# MYC_Homematic_FS20.net
KiCad netlist of a schematic drawn in EAGLE
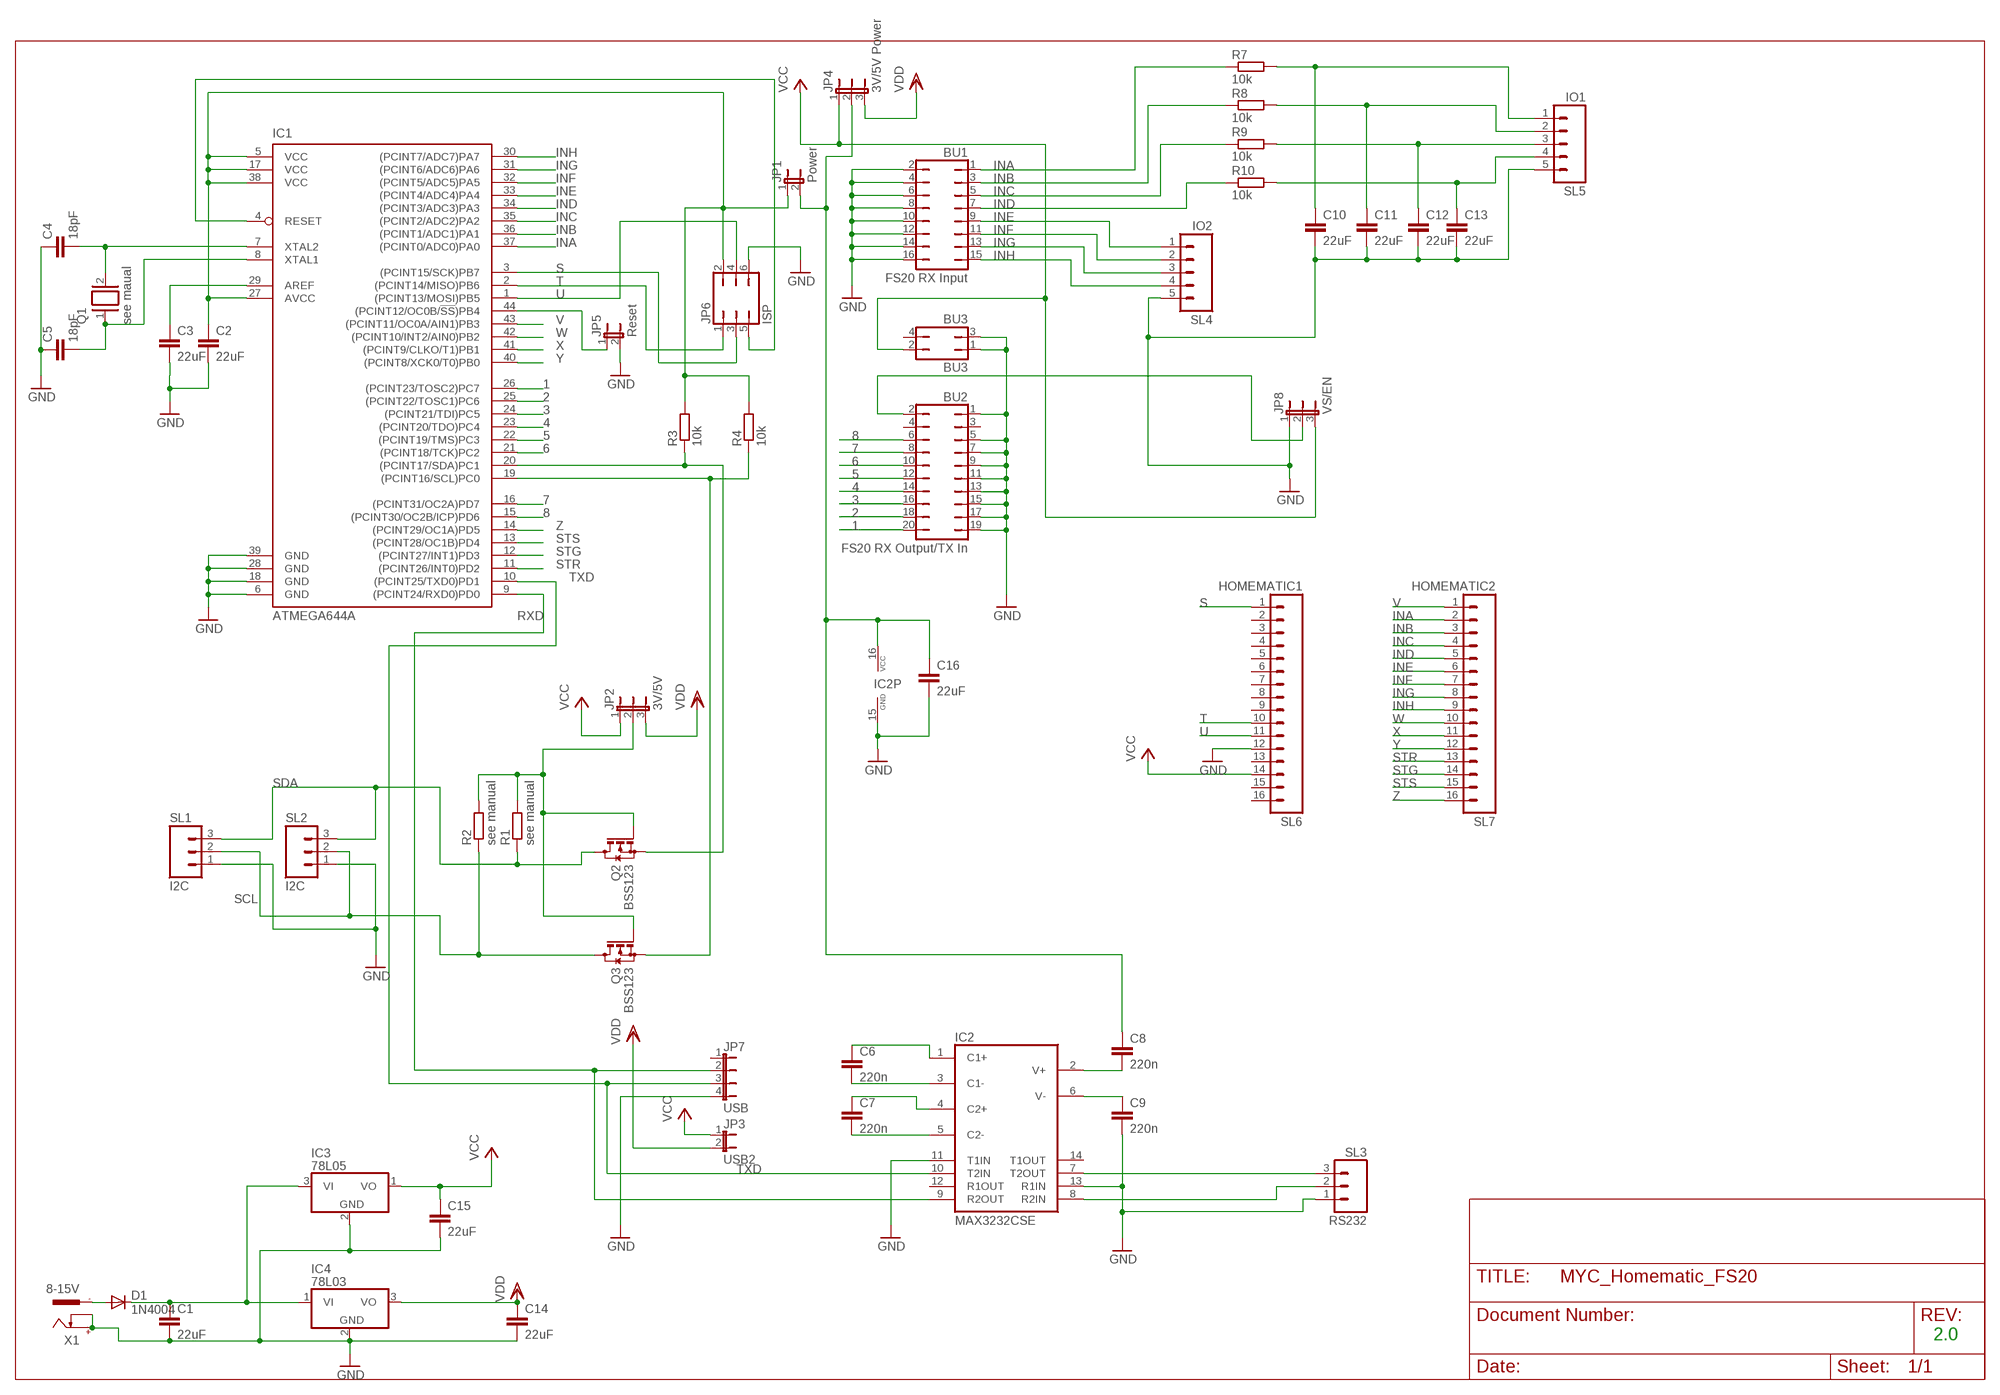
[diagram p0: schematic, sheet 1]

(export (version "E")
  (design (tool "Eeschema 10.0.6"))
  (components
    (comp (ref "BU1")
      (value "FS20 RX Input")
      (footprint "eagle-import:JP8Q")
      (libsource (lib "eagle-import") (part "JP8Q"))
    )
    (comp (ref "BU2")
      (value "FS20 RX Output/TX In")
      (footprint "eagle-import:JP10Q")
      (libsource (lib "eagle-import") (part "JP10Q"))
    )
    (comp (ref "BU3")
      (value "BU3")
      (footprint "eagle-import:JP2Q")
      (libsource (lib "eagle-import") (part "JP2Q"))
    )
    (comp (ref "C1")
      (value "22uF")
      (footprint "eagle-import:C1206")
      (libsource (lib "eagle-import") (part "C-EUC1206"))
    )
    (comp (ref "C2")
      (value "22uF")
      (footprint "eagle-import:C1206")
      (libsource (lib "eagle-import") (part "C-EUC1206"))
    )
    (comp (ref "C3")
      (value "22uF")
      (footprint "eagle-import:C1206")
      (libsource (lib "eagle-import") (part "C-EUC1206"))
    )
    (comp (ref "C4")
      (value "18pF")
      (footprint "eagle-import:C025-030X050")
      (libsource (lib "eagle-import") (part "C-EU025-030X050"))
    )
    (comp (ref "C5")
      (value "18pF")
      (footprint "eagle-import:C025-030X050")
      (libsource (lib "eagle-import") (part "C-EU025-030X050"))
    )
    (comp (ref "C6")
      (value "220n")
      (footprint "eagle-import:C1206")
      (libsource (lib "eagle-import") (part "C-EUC1206"))
    )
    (comp (ref "C7")
      (value "220n")
      (footprint "eagle-import:C1206")
      (libsource (lib "eagle-import") (part "C-EUC1206"))
    )
    (comp (ref "C8")
      (value "220n")
      (footprint "eagle-import:C1206")
      (libsource (lib "eagle-import") (part "C-EUC1206"))
    )
    (comp (ref "C9")
      (value "220n")
      (footprint "eagle-import:C1206")
      (libsource (lib "eagle-import") (part "C-EUC1206"))
    )
    (comp (ref "C10")
      (value "22uF")
      (footprint "eagle-import:C1206")
      (libsource (lib "eagle-import") (part "C-EUC1206"))
    )
    (comp (ref "C11")
      (value "22uF")
      (footprint "eagle-import:C1206")
      (libsource (lib "eagle-import") (part "C-EUC1206"))
    )
    (comp (ref "C12")
      (value "22uF")
      (footprint "eagle-import:C1206")
      (libsource (lib "eagle-import") (part "C-EUC1206"))
    )
    (comp (ref "C13")
      (value "22uF")
      (footprint "eagle-import:C1206")
      (libsource (lib "eagle-import") (part "C-EUC1206"))
    )
    (comp (ref "C14")
      (value "22uF")
      (footprint "eagle-import:C1206")
      (libsource (lib "eagle-import") (part "C-EUC1206"))
    )
    (comp (ref "C15")
      (value "22uF")
      (footprint "eagle-import:C1206")
      (libsource (lib "eagle-import") (part "C-EUC1206"))
    )
    (comp (ref "C16")
      (value "22uF")
      (footprint "eagle-import:C1206")
      (libsource (lib "eagle-import") (part "C-EUC1206"))
    )
    (comp (ref "D1")
      (value "1N4004")
      (footprint "eagle-import:DO41-10")
      (libsource (lib "eagle-import") (part "1N4004"))
    )
    (comp (ref "IC1")
      (value "ATMEGA644A")
      (footprint "eagle-import:TQFP44")
      (fields (field (name "MPN") "ATMEGA644PV-10AU"))
      (libsource (lib "eagle-import") (part "ATMEGA644A"))
    )
    (comp (ref "IC2")
      (value "MAX3232CSE")
      (footprint "eagle-import:SO16")
      (libsource (lib "eagle-import") (part "MAX3232SEC"))
    )
    (comp (ref "IC3")
      (value "78L05")
      (footprint "eagle-import:TO92")
      (libsource (lib "eagle-import") (part "78L05"))
    )
    (comp (ref "IC4")
      (value "78L03")
      (footprint "eagle-import:TO220V")
      (libsource (lib "eagle-import") (part "78TV05"))
    )
    (comp (ref "JP1")
      (value "Power")
      (footprint "eagle-import:JP1")
      (libsource (lib "eagle-import") (part "JP1E"))
    )
    (comp (ref "JP2")
      (value "3V/5V")
      (footprint "eagle-import:JP2")
      (libsource (lib "eagle-import") (part "JP2E"))
    )
    (comp (ref "JP3")
      (value "USB2")
      (footprint "eagle-import:JP1")
      (libsource (lib "eagle-import") (part "JP1E"))
    )
    (comp (ref "JP4")
      (value "3V/5V Power")
      (footprint "eagle-import:JP2")
      (libsource (lib "eagle-import") (part "JP2E"))
    )
    (comp (ref "JP5")
      (value "Reset")
      (footprint "eagle-import:JP1")
      (libsource (lib "eagle-import") (part "JP1E"))
    )
    (comp (ref "JP6")
      (value "ISP")
      (footprint "eagle-import:JP3Q")
      (libsource (lib "eagle-import") (part "JP3Q"))
    )
    (comp (ref "JP7")
      (value "USB")
      (footprint "eagle-import:JP4")
      (libsource (lib "eagle-import") (part "JP4E"))
    )
    (comp (ref "JP8")
      (value "VS/EN")
      (footprint "eagle-import:JP2")
      (libsource (lib "eagle-import") (part "JP2E"))
    )
    (comp (ref "Q1")
      (value "see maual")
      (footprint "eagle-import:QS")
      (libsource (lib "eagle-import") (part "XTAL/S"))
    )
    (comp (ref "Q2")
      (value "BSS123")
      (footprint "eagle-import:SOT23")
      (libsource (lib "eagle-import") (part "BSS123"))
    )
    (comp (ref "Q3")
      (value "BSS123")
      (footprint "eagle-import:SOT23")
      (libsource (lib "eagle-import") (part "BSS123"))
    )
    (comp (ref "R1")
      (value "see manual")
      (footprint "eagle-import:R1206")
      (libsource (lib "eagle-import") (part "R-EU_R1206"))
    )
    (comp (ref "R2")
      (value "see manual")
      (footprint "eagle-import:R1206")
      (libsource (lib "eagle-import") (part "R-EU_R1206"))
    )
    (comp (ref "R3")
      (value "10k")
      (footprint "eagle-import:R1206")
      (libsource (lib "eagle-import") (part "R-EU_R1206"))
    )
    (comp (ref "R4")
      (value "10k")
      (footprint "eagle-import:R1206")
      (libsource (lib "eagle-import") (part "R-EU_R1206"))
    )
    (comp (ref "R7")
      (value "10k")
      (footprint "eagle-import:R1206")
      (libsource (lib "eagle-import") (part "R-EU_R1206"))
    )
    (comp (ref "R8")
      (value "10k")
      (footprint "eagle-import:R1206")
      (libsource (lib "eagle-import") (part "R-EU_R1206"))
    )
    (comp (ref "R9")
      (value "10k")
      (footprint "eagle-import:R1206")
      (libsource (lib "eagle-import") (part "R-EU_R1206"))
    )
    (comp (ref "R10")
      (value "10k")
      (footprint "eagle-import:R1206")
      (libsource (lib "eagle-import") (part "R-EU_R1206"))
    )
    (comp (ref "SL1")
      (value "I2C")
      (footprint "eagle-import:03P")
      (libsource (lib "eagle-import") (part "M03"))
    )
    (comp (ref "SL2")
      (value "I2C")
      (footprint "eagle-import:03P")
      (libsource (lib "eagle-import") (part "M03"))
    )
    (comp (ref "SL3")
      (value "RS232")
      (footprint "eagle-import:03P")
      (libsource (lib "eagle-import") (part "M03"))
    )
    (comp (ref "SL4")
      (value "IO2")
      (footprint "eagle-import:05P")
      (libsource (lib "eagle-import") (part "M05"))
    )
    (comp (ref "SL5")
      (value "IO1")
      (footprint "eagle-import:05P")
      (libsource (lib "eagle-import") (part "M05"))
    )
    (comp (ref "SL6")
      (value "HOMEMATIC1")
      (footprint "eagle-import:16P")
      (libsource (lib "eagle-import") (part "M16"))
    )
    (comp (ref "SL7")
      (value "HOMEMATIC2")
      (footprint "eagle-import:16P")
      (libsource (lib "eagle-import") (part "M16"))
    )
    (comp (ref "X1")
      (value "8-15V")
      (footprint "eagle-import:737992-5")
      (libsource (lib "eagle-import") (part "737992-55"))
    )
  )
  (nets
    (net (code "1") (name "/1") (class "Default")
      (node (ref "BU2") (pin "20") (pinfunction "20_20") (pintype "passive"))
      (node (ref "IC1") (pin "26") (pinfunction "(PCINT23/TOSC2)PC7_26") (pintype "output"))
    )
    (net (code "2") (name "/2") (class "Default")
      (node (ref "BU2") (pin "18") (pinfunction "18_18") (pintype "passive"))
      (node (ref "IC1") (pin "25") (pinfunction "(PCINT22/TOSC1)PC6_25") (pintype "output"))
    )
    (net (code "3") (name "/3") (class "Default")
      (node (ref "BU2") (pin "16") (pinfunction "16_16") (pintype "passive"))
      (node (ref "IC1") (pin "24") (pinfunction "(PCINT21/TDI)PC5_24") (pintype "output"))
    )
    (net (code "4") (name "/4") (class "Default")
      (node (ref "BU2") (pin "14") (pinfunction "14_14") (pintype "passive"))
      (node (ref "IC1") (pin "23") (pinfunction "(PCINT20/TDO)PC4_23") (pintype "output"))
    )
    (net (code "5") (name "/5") (class "Default")
      (node (ref "BU2") (pin "12") (pinfunction "12_12") (pintype "passive"))
      (node (ref "IC1") (pin "22") (pinfunction "(PCINT19/TMS)PC3_22") (pintype "output"))
    )
    (net (code "6") (name "/6") (class "Default")
      (node (ref "BU2") (pin "10") (pinfunction "10_10") (pintype "passive"))
      (node (ref "IC1") (pin "21") (pinfunction "(PCINT18/TCK)PC2_21") (pintype "output"))
    )
    (net (code "7") (name "/7") (class "Default")
      (node (ref "BU2") (pin "8") (pinfunction "8_8") (pintype "passive"))
      (node (ref "IC1") (pin "16") (pinfunction "(PCINT31/OC2A)PD7_16") (pintype "bidirectional"))
    )
    (net (code "8") (name "/8") (class "Default")
      (node (ref "BU2") (pin "6") (pinfunction "6_6") (pintype "passive"))
      (node (ref "IC1") (pin "15") (pinfunction "(PCINT30/OC2B/ICP)PD6_15") (pintype "bidirectional"))
    )
    (net (code "9") (name "/INA") (class "Default")
      (node (ref "BU1") (pin "1") (pinfunction "1_1") (pintype "passive"))
      (node (ref "IC1") (pin "37") (pinfunction "(PCINT0/ADC0)PA0_37") (pintype "bidirectional"))
      (node (ref "R7") (pin "1") (pinfunction "1_1") (pintype "passive"))
      (node (ref "SL7") (pin "2") (pinfunction "2_2") (pintype "passive"))
    )
    (net (code "10") (name "/INB") (class "Default")
      (node (ref "BU1") (pin "3") (pinfunction "3_3") (pintype "passive"))
      (node (ref "IC1") (pin "36") (pinfunction "(PCINT1/ADC1)PA1_36") (pintype "bidirectional"))
      (node (ref "R8") (pin "1") (pinfunction "1_1") (pintype "passive"))
      (node (ref "SL7") (pin "3") (pinfunction "3_3") (pintype "passive"))
    )
    (net (code "11") (name "/INC") (class "Default")
      (node (ref "BU1") (pin "5") (pinfunction "5_5") (pintype "passive"))
      (node (ref "IC1") (pin "35") (pinfunction "(PCINT2/ADC2)PA2_35") (pintype "bidirectional"))
      (node (ref "R9") (pin "1") (pinfunction "1_1") (pintype "passive"))
      (node (ref "SL7") (pin "4") (pinfunction "4_4") (pintype "passive"))
    )
    (net (code "12") (name "/IND") (class "Default")
      (node (ref "BU1") (pin "7") (pinfunction "7_7") (pintype "passive"))
      (node (ref "IC1") (pin "34") (pinfunction "(PCINT3/ADC3)PA3_34") (pintype "bidirectional"))
      (node (ref "R10") (pin "1") (pinfunction "1_1") (pintype "passive"))
      (node (ref "SL7") (pin "5") (pinfunction "5_5") (pintype "passive"))
    )
    (net (code "13") (name "/INE") (class "Default")
      (node (ref "BU1") (pin "9") (pinfunction "9_9") (pintype "passive"))
      (node (ref "IC1") (pin "33") (pinfunction "(PCINT4/ADC4)PA4_33") (pintype "bidirectional"))
      (node (ref "SL4") (pin "1") (pinfunction "1_1") (pintype "passive"))
      (node (ref "SL7") (pin "6") (pinfunction "6_6") (pintype "passive"))
    )
    (net (code "14") (name "/INF") (class "Default")
      (node (ref "BU1") (pin "11") (pinfunction "11_11") (pintype "passive"))
      (node (ref "IC1") (pin "32") (pinfunction "(PCINT5/ADC5)PA5_32") (pintype "bidirectional"))
      (node (ref "SL4") (pin "2") (pinfunction "2_2") (pintype "passive"))
      (node (ref "SL7") (pin "7") (pinfunction "7_7") (pintype "passive"))
    )
    (net (code "15") (name "/ING") (class "Default")
      (node (ref "BU1") (pin "13") (pinfunction "13_13") (pintype "passive"))
      (node (ref "IC1") (pin "31") (pinfunction "(PCINT6/ADC6)PA6_31") (pintype "bidirectional"))
      (node (ref "SL4") (pin "3") (pinfunction "3_3") (pintype "passive"))
      (node (ref "SL7") (pin "8") (pinfunction "8_8") (pintype "passive"))
    )
    (net (code "16") (name "/INH") (class "Default")
      (node (ref "BU1") (pin "15") (pinfunction "15_15") (pintype "passive"))
      (node (ref "IC1") (pin "30") (pinfunction "(PCINT7/ADC7)PA7_30") (pintype "bidirectional"))
      (node (ref "SL4") (pin "4") (pinfunction "4_4") (pintype "passive"))
      (node (ref "SL7") (pin "9") (pinfunction "9_9") (pintype "passive"))
    )
    (net (code "17") (name "/RXD") (class "Default")
      (node (ref "IC1") (pin "9") (pinfunction "(PCINT24/RXD0)PD0_9") (pintype "bidirectional"))
      (node (ref "IC2") (pin "9") (pinfunction "R2OUT_9") (pintype "output"))
      (node (ref "JP7") (pin "2") (pinfunction "2_2") (pintype "passive"))
    )
    (net (code "18") (name "/S") (class "Default")
      (node (ref "IC1") (pin "3") (pinfunction "(PCINT15/SCK)PB7_3") (pintype "bidirectional"))
      (node (ref "JP6") (pin "3") (pinfunction "3_3") (pintype "passive"))
      (node (ref "SL6") (pin "1") (pinfunction "1_1") (pintype "passive"))
    )
    (net (code "19") (name "/SCL") (class "Default")
      (node (ref "Q3") (pin "3") (pinfunction "D_3") (pintype "passive"))
      (node (ref "R2") (pin "1") (pinfunction "1_1") (pintype "passive"))
      (node (ref "SL1") (pin "2") (pinfunction "2_2") (pintype "passive"))
      (node (ref "SL2") (pin "2") (pinfunction "2_2") (pintype "passive"))
    )
    (net (code "20") (name "/SDA") (class "Default")
      (node (ref "Q2") (pin "3") (pinfunction "D_3") (pintype "passive"))
      (node (ref "R1") (pin "1") (pinfunction "1_1") (pintype "passive"))
      (node (ref "SL1") (pin "3") (pinfunction "3_3") (pintype "passive"))
      (node (ref "SL2") (pin "3") (pinfunction "3_3") (pintype "passive"))
    )
    (net (code "21") (name "/STG") (class "Default")
      (node (ref "IC1") (pin "12") (pinfunction "(PCINT27/INT1)PD3_12") (pintype "bidirectional"))
      (node (ref "SL7") (pin "14") (pinfunction "14_14") (pintype "passive"))
    )
    (net (code "22") (name "/STR") (class "Default")
      (node (ref "IC1") (pin "11") (pinfunction "(PCINT26/INT0)PD2_11") (pintype "bidirectional"))
      (node (ref "SL7") (pin "13") (pinfunction "13_13") (pintype "passive"))
    )
    (net (code "23") (name "/STS") (class "Default")
      (node (ref "IC1") (pin "13") (pinfunction "(PCINT28/OC1B)PD4_13") (pintype "bidirectional"))
      (node (ref "SL7") (pin "15") (pinfunction "15_15") (pintype "passive"))
    )
    (net (code "24") (name "/T") (class "Default")
      (node (ref "IC1") (pin "2") (pinfunction "(PCINT14/MISO)PB6_2") (pintype "bidirectional"))
      (node (ref "JP6") (pin "1") (pinfunction "1_1") (pintype "passive"))
      (node (ref "SL6") (pin "10") (pinfunction "10_10") (pintype "passive"))
    )
    (net (code "25") (name "/TXD") (class "Default")
      (node (ref "IC1") (pin "10") (pinfunction "(PCINT25/TXD0)PD1_10") (pintype "bidirectional"))
      (node (ref "IC2") (pin "10") (pinfunction "T2IN_10") (pintype "input"))
      (node (ref "JP7") (pin "3") (pinfunction "3_3") (pintype "passive"))
    )
    (net (code "26") (name "/U") (class "Default")
      (node (ref "IC1") (pin "1") (pinfunction "(PCINT13/MOSI)PB5_1") (pintype "bidirectional"))
      (node (ref "JP6") (pin "4") (pinfunction "4_4") (pintype "passive"))
      (node (ref "SL6") (pin "11") (pinfunction "11_11") (pintype "passive"))
    )
    (net (code "27") (name "/V") (class "Default")
      (node (ref "IC1") (pin "43") (pinfunction "(PCINT11/OC0A/AIN1)PB3_43") (pintype "bidirectional"))
      (node (ref "SL7") (pin "1") (pinfunction "1_1") (pintype "passive"))
    )
    (net (code "28") (name "/W") (class "Default")
      (node (ref "IC1") (pin "42") (pinfunction "(PCINT10/INT2/AIN0)PB2_42") (pintype "bidirectional"))
      (node (ref "SL7") (pin "10") (pinfunction "10_10") (pintype "passive"))
    )
    (net (code "29") (name "/X") (class "Default")
      (node (ref "IC1") (pin "41") (pinfunction "(PCINT9/CLKO/T1)PB1_41") (pintype "bidirectional"))
      (node (ref "SL7") (pin "11") (pinfunction "11_11") (pintype "passive"))
    )
    (net (code "30") (name "/Y") (class "Default")
      (node (ref "IC1") (pin "40") (pinfunction "(PCINT8/XCK0/T0)PB0_40") (pintype "bidirectional"))
      (node (ref "SL7") (pin "12") (pinfunction "12_12") (pintype "passive"))
    )
    (net (code "31") (name "/Z") (class "Default")
      (node (ref "IC1") (pin "14") (pinfunction "(PCINT29/OC1A)PD5_14") (pintype "bidirectional"))
      (node (ref "SL7") (pin "16") (pinfunction "16_16") (pintype "passive"))
    )
    (net (code "32") (name "GND") (class "Default")
      (node (ref "BU1") (pin "10") (pinfunction "10_10") (pintype "passive"))
      (node (ref "BU1") (pin "12") (pinfunction "12_12") (pintype "passive"))
      (node (ref "BU1") (pin "14") (pinfunction "14_14") (pintype "passive"))
      (node (ref "BU1") (pin "16") (pinfunction "16_16") (pintype "passive"))
      (node (ref "BU1") (pin "2") (pinfunction "2_2") (pintype "passive"))
      (node (ref "BU1") (pin "4") (pinfunction "4_4") (pintype "passive"))
      (node (ref "BU1") (pin "6") (pinfunction "6_6") (pintype "passive"))
      (node (ref "BU1") (pin "8") (pinfunction "8_8") (pintype "passive"))
      (node (ref "BU2") (pin "1") (pinfunction "1_1") (pintype "passive"))
      (node (ref "BU2") (pin "11") (pinfunction "11_11") (pintype "passive"))
      (node (ref "BU2") (pin "13") (pinfunction "13_13") (pintype "passive"))
      (node (ref "BU2") (pin "15") (pinfunction "15_15") (pintype "passive"))
      (node (ref "BU2") (pin "17") (pinfunction "17_17") (pintype "passive"))
      (node (ref "BU2") (pin "19") (pinfunction "19_19") (pintype "passive"))
      (node (ref "BU2") (pin "5") (pinfunction "5_5") (pintype "passive"))
      (node (ref "BU2") (pin "7") (pinfunction "7_7") (pintype "passive"))
      (node (ref "BU2") (pin "9") (pinfunction "9_9") (pintype "passive"))
      (node (ref "BU3") (pin "1") (pinfunction "1_1") (pintype "passive"))
      (node (ref "BU3") (pin "3") (pinfunction "3_3") (pintype "passive"))
      (node (ref "C1") (pin "2") (pinfunction "2_2") (pintype "passive"))
      (node (ref "C10") (pin "2") (pinfunction "2_2") (pintype "passive"))
      (node (ref "C11") (pin "2") (pinfunction "2_2") (pintype "passive"))
      (node (ref "C12") (pin "2") (pinfunction "2_2") (pintype "passive"))
      (node (ref "C13") (pin "2") (pinfunction "2_2") (pintype "passive"))
      (node (ref "C14") (pin "2") (pinfunction "2_2") (pintype "passive"))
      (node (ref "C15") (pin "2") (pinfunction "2_2") (pintype "passive"))
      (node (ref "C16") (pin "2") (pinfunction "2_2") (pintype "passive"))
      (node (ref "C2") (pin "2") (pinfunction "2_2") (pintype "passive"))
      (node (ref "C3") (pin "2") (pinfunction "2_2") (pintype "passive"))
      (node (ref "C4") (pin "1") (pinfunction "1_1") (pintype "passive"))
      (node (ref "C5") (pin "1") (pinfunction "1_1") (pintype "passive"))
      (node (ref "C9") (pin "2") (pinfunction "2_2") (pintype "passive"))
      (node (ref "IC1") (pin "18") (pinfunction "GND_18") (pintype "power_in"))
      (node (ref "IC1") (pin "28") (pinfunction "GND_28") (pintype "power_in"))
      (node (ref "IC1") (pin "39") (pinfunction "GND_39") (pintype "power_in"))
      (node (ref "IC1") (pin "6") (pinfunction "GND_6") (pintype "power_in"))
      (node (ref "IC2") (pin "11") (pinfunction "T1IN_11") (pintype "input"))
      (node (ref "IC2") (pin "13") (pinfunction "R1IN_13") (pintype "input"))
      (node (ref "IC2") (pin "15") (pinfunction "GND_15") (pintype "power_in"))
      (node (ref "IC3") (pin "2") (pinfunction "GND_2") (pintype "passive"))
      (node (ref "IC4") (pin "2") (pinfunction "GND_2") (pintype "passive"))
      (node (ref "JP5") (pin "2") (pinfunction "2_2") (pintype "passive"))
      (node (ref "JP6") (pin "6") (pinfunction "6_6") (pintype "passive"))
      (node (ref "JP7") (pin "4") (pinfunction "4_4") (pintype "passive"))
      (node (ref "JP8") (pin "1") (pinfunction "1_1") (pintype "passive"))
      (node (ref "SL1") (pin "1") (pinfunction "1_1") (pintype "passive"))
      (node (ref "SL2") (pin "1") (pinfunction "1_1") (pintype "passive"))
      (node (ref "SL3") (pin "1") (pinfunction "1_1") (pintype "passive"))
      (node (ref "SL4") (pin "5") (pinfunction "5_5") (pintype "passive"))
      (node (ref "SL5") (pin "5") (pinfunction "5_5") (pintype "passive"))
      (node (ref "SL6") (pin "12") (pinfunction "12_12") (pintype "passive"))
      (node (ref "X1") (pin "+") (pinfunction "+_+") (pintype "passive"))
      (node (ref "X1") (pin "K") (pinfunction "K_K") (pintype "passive"))
    )
    (net (code "33") (name "Net-(BU2-Pad2)") (class "Default")
      (node (ref "BU2") (pin "2") (pinfunction "2_2") (pintype "passive"))
      (node (ref "JP8") (pin "2") (pinfunction "2_2") (pintype "passive"))
    )
    (net (code "34") (name "Net-(C10-Pad1)") (class "Default")
      (node (ref "C10") (pin "1") (pinfunction "1_1") (pintype "passive"))
      (node (ref "R7") (pin "2") (pinfunction "2_2") (pintype "passive"))
      (node (ref "SL5") (pin "1") (pinfunction "1_1") (pintype "passive"))
    )
    (net (code "35") (name "Net-(C11-Pad1)") (class "Default")
      (node (ref "C11") (pin "1") (pinfunction "1_1") (pintype "passive"))
      (node (ref "R8") (pin "2") (pinfunction "2_2") (pintype "passive"))
      (node (ref "SL5") (pin "2") (pinfunction "2_2") (pintype "passive"))
    )
    (net (code "36") (name "Net-(C12-Pad1)") (class "Default")
      (node (ref "C12") (pin "1") (pinfunction "1_1") (pintype "passive"))
      (node (ref "R9") (pin "2") (pinfunction "2_2") (pintype "passive"))
      (node (ref "SL5") (pin "3") (pinfunction "3_3") (pintype "passive"))
    )
    (net (code "37") (name "Net-(C13-Pad1)") (class "Default")
      (node (ref "C13") (pin "1") (pinfunction "1_1") (pintype "passive"))
      (node (ref "R10") (pin "2") (pinfunction "2_2") (pintype "passive"))
      (node (ref "SL5") (pin "4") (pinfunction "4_4") (pintype "passive"))
    )
    (net (code "38") (name "Net-(D1-PadA)") (class "Default")
      (node (ref "D1") (pin "A") (pinfunction "A_A") (pintype "passive"))
      (node (ref "X1") (pin "-1") (pinfunction "-1_-1") (pintype "passive"))
    )
    (net (code "39") (name "Net-(IC1-(PCINT12{slash}OC0B{slash}~{SS})PB4)") (class "Default")
      (node (ref "IC1") (pin "44") (pinfunction "(PCINT12/OC0B/~{SS})PB4_44") (pintype "bidirectional"))
      (node (ref "JP5") (pin "1") (pinfunction "1_1") (pintype "passive"))
    )
    (net (code "40") (name "Net-(IC1-(PCINT16{slash}SCL)PC0)") (class "Default")
      (node (ref "IC1") (pin "19") (pinfunction "(PCINT16/SCL)PC0_19") (pintype "output"))
      (node (ref "Q3") (pin "2") (pinfunction "S_2") (pintype "passive"))
      (node (ref "R4") (pin "1") (pinfunction "1_1") (pintype "passive"))
    )
    (net (code "41") (name "Net-(IC1-(PCINT17{slash}SDA)PC1)") (class "Default")
      (node (ref "IC1") (pin "20") (pinfunction "(PCINT17/SDA)PC1_20") (pintype "output"))
      (node (ref "Q2") (pin "2") (pinfunction "S_2") (pintype "passive"))
      (node (ref "R3") (pin "1") (pinfunction "1_1") (pintype "passive"))
    )
    (net (code "42") (name "Net-(IC1-AREF)") (class "Default")
      (node (ref "C3") (pin "1") (pinfunction "1_1") (pintype "passive"))
      (node (ref "IC1") (pin "29") (pinfunction "AREF_29") (pintype "passive"))
    )
    (net (code "43") (name "Net-(IC1-AVCC)") (class "Default")
      (node (ref "C2") (pin "1") (pinfunction "1_1") (pintype "passive"))
      (node (ref "IC1") (pin "17") (pinfunction "VCC_17") (pintype "power_in"))
      (node (ref "IC1") (pin "27") (pinfunction "AVCC_27") (pintype "power_in"))
      (node (ref "IC1") (pin "38") (pinfunction "VCC_38") (pintype "power_in"))
      (node (ref "IC1") (pin "5") (pinfunction "VCC_5") (pintype "power_in"))
      (node (ref "JP1") (pin "1") (pinfunction "1_1") (pintype "passive"))
      (node (ref "JP6") (pin "2") (pinfunction "2_2") (pintype "passive"))
      (node (ref "R3") (pin "2") (pinfunction "2_2") (pintype "passive"))
      (node (ref "R4") (pin "2") (pinfunction "2_2") (pintype "passive"))
    )
    (net (code "44") (name "Net-(IC1-RESET)") (class "Default")
      (node (ref "IC1") (pin "4") (pinfunction "RESET_4") (pintype "input"))
      (node (ref "JP6") (pin "5") (pinfunction "5_5") (pintype "passive"))
    )
    (net (code "45") (name "Net-(IC1-XTAL1)") (class "Default")
      (node (ref "C5") (pin "2") (pinfunction "2_2") (pintype "passive"))
      (node (ref "IC1") (pin "8") (pinfunction "XTAL1_8") (pintype "bidirectional"))
      (node (ref "Q1") (pin "1") (pinfunction "1_1") (pintype "passive"))
    )
    (net (code "46") (name "Net-(IC1-XTAL2)") (class "Default")
      (node (ref "C4") (pin "2") (pinfunction "2_2") (pintype "passive"))
      (node (ref "IC1") (pin "7") (pinfunction "XTAL2_7") (pintype "bidirectional"))
      (node (ref "Q1") (pin "2") (pinfunction "2_2") (pintype "passive"))
    )
    (net (code "47") (name "Net-(IC2A-C1+)") (class "Default")
      (node (ref "C6") (pin "1") (pinfunction "1_1") (pintype "passive"))
      (node (ref "IC2") (pin "1") (pinfunction "C1+_1") (pintype "bidirectional"))
    )
    (net (code "48") (name "Net-(IC2A-C1-)") (class "Default")
      (node (ref "C6") (pin "2") (pinfunction "2_2") (pintype "passive"))
      (node (ref "IC2") (pin "3") (pinfunction "C1-_3") (pintype "bidirectional"))
    )
    (net (code "49") (name "Net-(IC2A-C2+)") (class "Default")
      (node (ref "C7") (pin "1") (pinfunction "1_1") (pintype "passive"))
      (node (ref "IC2") (pin "4") (pinfunction "C2+_4") (pintype "bidirectional"))
    )
    (net (code "50") (name "Net-(IC2A-C2-)") (class "Default")
      (node (ref "C7") (pin "2") (pinfunction "2_2") (pintype "passive"))
      (node (ref "IC2") (pin "5") (pinfunction "C2-_5") (pintype "bidirectional"))
    )
    (net (code "51") (name "Net-(IC2A-R2IN)") (class "Default")
      (node (ref "IC2") (pin "8") (pinfunction "R2IN_8") (pintype "input"))
      (node (ref "SL3") (pin "2") (pinfunction "2_2") (pintype "passive"))
    )
    (net (code "52") (name "Net-(IC2A-T2OUT)") (class "Default")
      (node (ref "IC2") (pin "7") (pinfunction "T2OUT_7") (pintype "output"))
      (node (ref "SL3") (pin "3") (pinfunction "3_3") (pintype "passive"))
    )
    (net (code "53") (name "Net-(IC2A-V+)") (class "Default")
      (node (ref "C8") (pin "2") (pinfunction "2_2") (pintype "passive"))
      (node (ref "IC2") (pin "2") (pinfunction "V+_2") (pintype "bidirectional"))
    )
    (net (code "54") (name "Net-(IC2A-V-)") (class "Default")
      (node (ref "C9") (pin "1") (pinfunction "1_1") (pintype "passive"))
      (node (ref "IC2") (pin "6") (pinfunction "V-_6") (pintype "bidirectional"))
    )
    (net (code "55") (name "Net-(IC2B-VCC)") (class "Default")
      (node (ref "C16") (pin "1") (pinfunction "1_1") (pintype "passive"))
      (node (ref "C8") (pin "1") (pinfunction "1_1") (pintype "passive"))
      (node (ref "IC2") (pin "16") (pinfunction "VCC_16") (pintype "power_in"))
      (node (ref "JP1") (pin "2") (pinfunction "2_2") (pintype "passive"))
      (node (ref "JP4") (pin "2") (pinfunction "2_2") (pintype "passive"))
    )
    (net (code "56") (name "Net-(IC3-VI)") (class "Default")
      (node (ref "C1") (pin "1") (pinfunction "1_1") (pintype "passive"))
      (node (ref "D1") (pin "C") (pinfunction "C_C") (pintype "passive"))
      (node (ref "IC3") (pin "3") (pinfunction "VI_3") (pintype "input"))
      (node (ref "IC4") (pin "1") (pinfunction "VI_1") (pintype "input"))
    )
    (net (code "57") (name "Net-(Q2-G)") (class "Default")
      (node (ref "JP2") (pin "2") (pinfunction "2_2") (pintype "passive"))
      (node (ref "Q2") (pin "1") (pinfunction "G_1") (pintype "passive"))
      (node (ref "Q3") (pin "1") (pinfunction "G_1") (pintype "passive"))
      (node (ref "R1") (pin "2") (pinfunction "2_2") (pintype "passive"))
      (node (ref "R2") (pin "2") (pinfunction "2_2") (pintype "passive"))
    )
    (net (code "58") (name "VCC") (class "Default")
      (node (ref "BU3") (pin "2") (pinfunction "2_2") (pintype "passive"))
      (node (ref "C15") (pin "1") (pinfunction "1_1") (pintype "passive"))
      (node (ref "IC3") (pin "1") (pinfunction "VO_1") (pintype "passive"))
      (node (ref "JP2") (pin "1") (pinfunction "1_1") (pintype "passive"))
      (node (ref "JP3") (pin "1") (pinfunction "1_1") (pintype "passive"))
      (node (ref "JP4") (pin "1") (pinfunction "1_1") (pintype "passive"))
      (node (ref "JP8") (pin "3") (pinfunction "3_3") (pintype "passive"))
      (node (ref "SL6") (pin "14") (pinfunction "14_14") (pintype "passive"))
    )
    (net (code "59") (name "VDD") (class "Default")
      (node (ref "C14") (pin "1") (pinfunction "1_1") (pintype "passive"))
      (node (ref "IC4") (pin "3") (pinfunction "VO_3") (pintype "passive"))
      (node (ref "JP2") (pin "3") (pinfunction "3_3") (pintype "passive"))
      (node (ref "JP3") (pin "2") (pinfunction "2_2") (pintype "passive"))
      (node (ref "JP4") (pin "3") (pinfunction "3_3") (pintype "passive"))
    )
    (net (code "60") (name "unconnected-(BU2-Pad3)") (class "Default")
      (node (ref "BU2") (pin "3") (pinfunction "3_3") (pintype "passive"))
    )
    (net (code "61") (name "unconnected-(BU2-Pad4)") (class "Default")
      (node (ref "BU2") (pin "4") (pinfunction "4_4") (pintype "passive"))
    )
    (net (code "62") (name "unconnected-(BU3-Pad4)") (class "Default")
      (node (ref "BU3") (pin "4") (pinfunction "4_4") (pintype "passive"))
    )
    (net (code "63") (name "unconnected-(IC2A-R1OUT-Pad12)") (class "Default")
      (node (ref "IC2") (pin "12") (pinfunction "R1OUT_12") (pintype "output"))
    )
    (net (code "64") (name "unconnected-(IC2A-T1OUT-Pad14)") (class "Default")
      (node (ref "IC2") (pin "14") (pinfunction "T1OUT_14") (pintype "output"))
    )
    (net (code "65") (name "unconnected-(JP7-Pad1)") (class "Default")
      (node (ref "JP7") (pin "1") (pinfunction "1_1") (pintype "passive"))
    )
    (net (code "66") (name "unconnected-(SL6-Pad2)") (class "Default")
      (node (ref "SL6") (pin "2") (pinfunction "2_2") (pintype "passive"))
    )
    (net (code "67") (name "unconnected-(SL6-Pad3)") (class "Default")
      (node (ref "SL6") (pin "3") (pinfunction "3_3") (pintype "passive"))
    )
    (net (code "68") (name "unconnected-(SL6-Pad4)") (class "Default")
      (node (ref "SL6") (pin "4") (pinfunction "4_4") (pintype "passive"))
    )
    (net (code "69") (name "unconnected-(SL6-Pad5)") (class "Default")
      (node (ref "SL6") (pin "5") (pinfunction "5_5") (pintype "passive"))
    )
    (net (code "70") (name "unconnected-(SL6-Pad6)") (class "Default")
      (node (ref "SL6") (pin "6") (pinfunction "6_6") (pintype "passive"))
    )
    (net (code "71") (name "unconnected-(SL6-Pad7)") (class "Default")
      (node (ref "SL6") (pin "7") (pinfunction "7_7") (pintype "passive"))
    )
    (net (code "72") (name "unconnected-(SL6-Pad8)") (class "Default")
      (node (ref "SL6") (pin "8") (pinfunction "8_8") (pintype "passive"))
    )
    (net (code "73") (name "unconnected-(SL6-Pad9)") (class "Default")
      (node (ref "SL6") (pin "9") (pinfunction "9_9") (pintype "passive"))
    )
    (net (code "74") (name "unconnected-(SL6-Pad13)") (class "Default")
      (node (ref "SL6") (pin "13") (pinfunction "13_13") (pintype "passive"))
    )
    (net (code "75") (name "unconnected-(SL6-Pad15)") (class "Default")
      (node (ref "SL6") (pin "15") (pinfunction "15_15") (pintype "passive"))
    )
    (net (code "76") (name "unconnected-(SL6-Pad16)") (class "Default")
      (node (ref "SL6") (pin "16") (pinfunction "16_16") (pintype "passive"))
    )
    (net (code "77") (name "unconnected-(X1-Pad-2)") (class "Default")
      (node (ref "X1") (pin "-2") (pinfunction "-2_-2") (pintype "passive"))
    )
  )
)
